# Power.net
KiCad netlist of a schematic drawn in Altium Designer
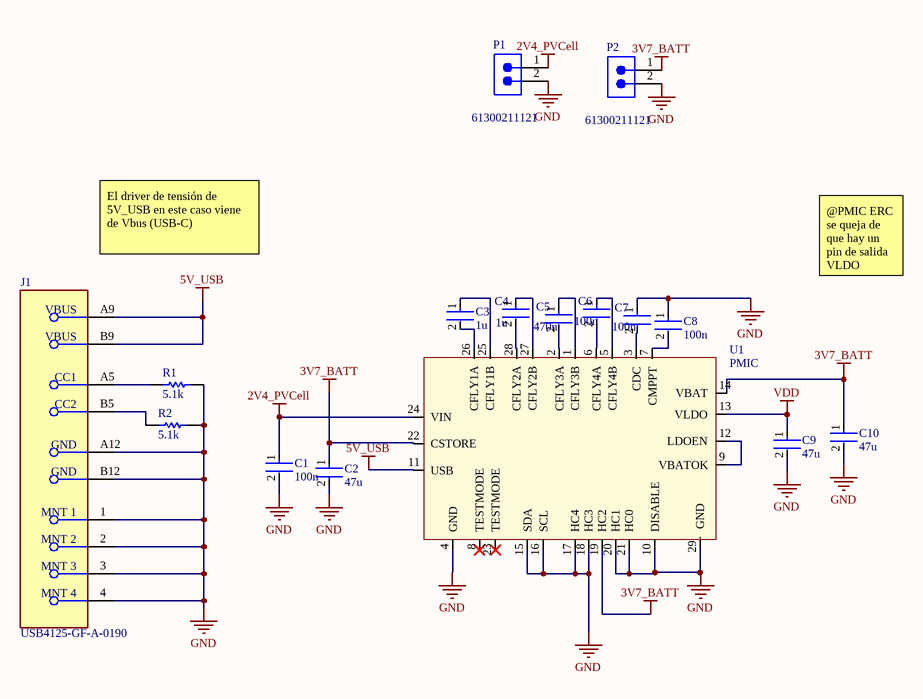
[diagram p0: Power.SchDoc]

(export (version "E")
  (design (tool "Eeschema 10.0.6"))
  (components
    (comp (ref "C1")
      (value "100n")
      (footprint "FP-GRM033-0_03-MFG")
      (description "Chip Multilayer Ceramic Capacitors for General Purpose, 0201, 0.10uF, X7S, 22%, 10%, 16V")
      (fields (field (name "TOLERANCE") "10%"))
      (libsource (lib "Altium Content Vault") (part "b4654b650e69147ec39a6b967a45e02"))
    )
    (comp (ref "C2")
      (value "47u")
      (footprint "FP-GRM188-0_2-IPC_B")
      (description "Chip Multilayer Ceramic Capacitors for General Purpose, 0603, 47uF, X5R, 15%, 20%, 6.3V")
      (fields (field (name "TOLERANCE") "20%"))
      (libsource (lib "Altium Content Vault") (part "11868f565c42a9108669ba33697ecf6"))
    )
    (comp (ref "C3")
      (value "1u")
      (footprint "FP-GRM033-0_05-e01_0_2-IPC_B")
      (description "Chip Multilayer Ceramic Capacitors for General Purpose, 0201, 1.0uF, X5R, 15%, 20%, 6.3V")
      (fields (field (name "TOLERANCE") "20%") (field (name "VOLTAGE") "6.3V"))
      (libsource (lib "Altium Content Vault") (part "02cd4be3c70576c341d710602a673aa"))
    )
    (comp (ref "C4")
      (value "1u")
      (footprint "FP-GRM033-0_05-e01_0_2-IPC_B")
      (description "Chip Multilayer Ceramic Capacitors for General Purpose, 0201, 1.0uF, X5R, 15%, 20%, 6.3V")
      (fields (field (name "TOLERANCE") "20%") (field (name "VOLTAGE") "6.3V"))
      (libsource (lib "Altium Content Vault") (part "02cd4be3c70576c341d710602a673aa"))
    )
    (comp (ref "C5")
      (value "470n")
      (footprint "FP-GRM033-0_03-IPC_C")
      (description "Chip Multilayer Ceramic Capacitors for General Purpose, 0201, 0.47uF, X5R, 15%, 10%, 6.3V")
      (fields (field (name "TOLERANCE") "10%"))
      (libsource (lib "Altium Content Vault") (part "b4654b650e69147ec39a6b967a45e02"))
    )
    (comp (ref "C6")
      (value "100n")
      (footprint "FP-GRM033-0_03-MFG")
      (description "Chip Multilayer Ceramic Capacitors for General Purpose, 0201, 0.10uF, X7S, 22%, 10%, 16V")
      (fields (field (name "TOLERANCE") "10%"))
      (libsource (lib "Altium Content Vault") (part "b4654b650e69147ec39a6b967a45e02"))
    )
    (comp (ref "C7")
      (value "100n")
      (footprint "FP-GRM033-0_03-MFG")
      (description "Chip Multilayer Ceramic Capacitors for General Purpose, 0201, 0.10uF, X7S, 22%, 10%, 16V")
      (fields (field (name "TOLERANCE") "10%"))
      (libsource (lib "Altium Content Vault") (part "b4654b650e69147ec39a6b967a45e02"))
    )
    (comp (ref "C8")
      (value "100n")
      (footprint "FP-GRM033-0_03-MFG")
      (description "Chip Multilayer Ceramic Capacitors for General Purpose, 0201, 0.10uF, X7S, 22%, 10%, 16V")
      (fields (field (name "TOLERANCE") "10%"))
      (libsource (lib "Altium Content Vault") (part "b4654b650e69147ec39a6b967a45e02"))
    )
    (comp (ref "C9")
      (value "47u")
      (footprint "FP-GRM188-0_2-IPC_B")
      (description "Chip Multilayer Ceramic Capacitors for General Purpose, 0603, 47uF, X5R, 15%, 20%, 6.3V")
      (fields (field (name "TOLERANCE") "20%"))
      (libsource (lib "Altium Content Vault") (part "11868f565c42a9108669ba33697ecf6"))
    )
    (comp (ref "C10")
      (value "47u")
      (footprint "FP-GRM188-0_2-IPC_B")
      (description "Chip Multilayer Ceramic Capacitors for General Purpose, 0603, 47uF, X5R, 15%, 20%, 6.3V")
      (fields (field (name "TOLERANCE") "20%"))
      (libsource (lib "Altium Content Vault") (part "11868f565c42a9108669ba33697ecf6"))
    )
    (comp (ref "J1")
      (value "USB4125-GF-A-0190")
      (footprint "FP-USB4125-GF-A-0190-MFG")
      (description "CONN RCPT TYPE C 6P SMD RA")
      (libsource (lib "Altium Content Vault") (part "a055484d46e58b234844902c9fd883a"))
    )
    (comp (ref "P1")
      (value "61300211121")
      (footprint "61300211121")
      (libsource (lib "Altium Content Vault") (part "Header_Male_1R_02P"))
    )
    (comp (ref "P2")
      (value "61300211121")
      (footprint "61300211121")
      (libsource (lib "Altium Content Vault") (part "Header_Male_1R_02P"))
    )
    (comp (ref "R1")
      (value "5.1k")
      (footprint "RESC1608X55X25ML10T15")
      (fields (field (name "MANUFACTURER") "Yageo") (field (name "PART NUMBER") "RC0603FR-075K1L"))
      (libsource (lib "Altium Content Vault") (part "RES"))
    )
    (comp (ref "R2")
      (value "5.1k")
      (footprint "RESC1608X55X25ML10T15")
      (fields (field (name "MANUFACTURER") "Yageo") (field (name "PART NUMBER") "RC0603FR-075K1L"))
      (libsource (lib "Altium Content Vault") (part "RES"))
    )
    (comp (ref "U1") (value "PMIC") (footprint "HVQFN-28") (libsource (lib "DEOP2425") (part "NEH7100BU")))
  )
  (nets
    (net (code "1") (name "2V4_PVCell") (class "Default")
      (node (ref "C1") (pin "1") (pinfunction "1_1") (pintype "passive"))
      (node (ref "P1") (pin "1") (pinfunction "1_1") (pintype "passive"))
      (node (ref "U1") (pin "24") (pinfunction "VIN_24") (pintype "power_in"))
    )
    (net (code "2") (name "3V7_BATT") (class "Default")
      (node (ref "C10") (pin "1") (pinfunction "1_1") (pintype "passive"))
      (node (ref "C2") (pin "1") (pinfunction "1_1") (pintype "passive"))
      (node (ref "P2") (pin "1") (pinfunction "1_1") (pintype "passive"))
      (node (ref "U1") (pin "14") (pinfunction "VBAT_14") (pintype "output"))
      (node (ref "U1") (pin "19") (pinfunction "HC2_19") (pintype "passive"))
      (node (ref "U1") (pin "22") (pinfunction "CSTORE_22") (pintype "passive"))
    )
    (net (code "3") (name "5V_USB") (class "Default")
      (node (ref "J1") (pin "A9") (pinfunction "VBUS_A9") (pintype "passive"))
      (node (ref "J1") (pin "B9") (pinfunction "VBUS_B9") (pintype "passive"))
      (node (ref "U1") (pin "11") (pinfunction "USB_11") (pintype "input"))
    )
    (net (code "4") (name "GND") (class "Default")
      (node (ref "C1") (pin "2") (pinfunction "2_2") (pintype "passive"))
      (node (ref "C10") (pin "2") (pinfunction "2_2") (pintype "passive"))
      (node (ref "C2") (pin "2") (pinfunction "2_2") (pintype "passive"))
      (node (ref "C7") (pin "1") (pinfunction "1_1") (pintype "passive"))
      (node (ref "C8") (pin "1") (pinfunction "1_1") (pintype "passive"))
      (node (ref "C9") (pin "2") (pinfunction "2_2") (pintype "passive"))
      (node (ref "J1") (pin "1") (pinfunction "MNT_1_1") (pintype "passive"))
      (node (ref "J1") (pin "2") (pinfunction "MNT_2_2") (pintype "passive"))
      (node (ref "J1") (pin "3") (pinfunction "MNT_3_3") (pintype "passive"))
      (node (ref "J1") (pin "4") (pinfunction "MNT_4_4") (pintype "passive"))
      (node (ref "J1") (pin "A12") (pinfunction "GND_A12") (pintype "passive"))
      (node (ref "J1") (pin "B12") (pinfunction "GND_B12") (pintype "passive"))
      (node (ref "P1") (pin "2") (pinfunction "2_2") (pintype "passive"))
      (node (ref "P2") (pin "2") (pinfunction "2_2") (pintype "passive"))
      (node (ref "R1") (pin "2") (pinfunction "2_2") (pintype "passive"))
      (node (ref "R2") (pin "2") (pinfunction "2_2") (pintype "passive"))
      (node (ref "U1") (pin "10") (pinfunction "DISABLE_10") (pintype "passive"))
      (node (ref "U1") (pin "15") (pinfunction "SDA_15") (pintype "bidirectional"))
      (node (ref "U1") (pin "16") (pinfunction "SCL_16") (pintype "input"))
      (node (ref "U1") (pin "17") (pinfunction "HC4_17") (pintype "passive"))
      (node (ref "U1") (pin "18") (pinfunction "HC3_18") (pintype "passive"))
      (node (ref "U1") (pin "21") (pinfunction "HC0_21") (pintype "passive"))
      (node (ref "U1") (pin "29") (pinfunction "GND_29") (pintype "passive"))
      (node (ref "U1") (pin "4") (pinfunction "GND_4") (pintype "input"))
    )
    (net (code "5") (name "Net-(J1-CC1)") (class "Default")
      (node (ref "J1") (pin "A5") (pinfunction "CC1_A5") (pintype "passive"))
      (node (ref "R1") (pin "1") (pinfunction "1_1") (pintype "passive"))
    )
    (net (code "6") (name "Net-(J1-CC2)") (class "Default")
      (node (ref "J1") (pin "B5") (pinfunction "CC2_B5") (pintype "passive"))
      (node (ref "R2") (pin "1") (pinfunction "1_1") (pintype "passive"))
    )
    (net (code "7") (name "Net-(U1-CDC)") (class "Default")
      (node (ref "C7") (pin "2") (pinfunction "2_2") (pintype "passive"))
      (node (ref "U1") (pin "3") (pinfunction "CDC_3") (pintype "passive"))
    )
    (net (code "8") (name "Net-(U1-CFLY1A)") (class "Default")
      (node (ref "C3") (pin "2") (pinfunction "2_2") (pintype "passive"))
      (node (ref "U1") (pin "26") (pinfunction "CFLY1A_26") (pintype "passive"))
    )
    (net (code "9") (name "Net-(U1-CFLY1B)") (class "Default")
      (node (ref "C3") (pin "1") (pinfunction "1_1") (pintype "passive"))
      (node (ref "U1") (pin "25") (pinfunction "CFLY1B_25") (pintype "passive"))
    )
    (net (code "10") (name "Net-(U1-CFLY2A)") (class "Default")
      (node (ref "C4") (pin "2") (pinfunction "2_2") (pintype "passive"))
      (node (ref "U1") (pin "28") (pinfunction "CFLY2A_28") (pintype "passive"))
    )
    (net (code "11") (name "Net-(U1-CFLY2B)") (class "Default")
      (node (ref "C4") (pin "1") (pinfunction "1_1") (pintype "passive"))
      (node (ref "U1") (pin "27") (pinfunction "CFLY2B_27") (pintype "passive"))
    )
    (net (code "12") (name "Net-(U1-CFLY3A)") (class "Default")
      (node (ref "C5") (pin "2") (pinfunction "2_2") (pintype "passive"))
      (node (ref "U1") (pin "2") (pinfunction "CFLY3A_2") (pintype "passive"))
    )
    (net (code "13") (name "Net-(U1-CFLY3B)") (class "Default")
      (node (ref "C5") (pin "1") (pinfunction "1_1") (pintype "passive"))
      (node (ref "U1") (pin "1") (pinfunction "CFLY3B_1") (pintype "passive"))
    )
    (net (code "14") (name "Net-(U1-CFLY4A)") (class "Default")
      (node (ref "C6") (pin "2") (pinfunction "2_2") (pintype "passive"))
      (node (ref "U1") (pin "6") (pinfunction "CFLY4A_6") (pintype "passive"))
    )
    (net (code "15") (name "Net-(U1-CFLY4B)") (class "Default")
      (node (ref "C6") (pin "1") (pinfunction "1_1") (pintype "passive"))
      (node (ref "U1") (pin "5") (pinfunction "CFLY4B_5") (pintype "passive"))
    )
    (net (code "16") (name "Net-(U1-CMPPT)") (class "Default")
      (node (ref "C8") (pin "2") (pinfunction "2_2") (pintype "passive"))
      (node (ref "U1") (pin "7") (pinfunction "CMPPT_7") (pintype "passive"))
    )
    (net (code "17") (name "Net-(U1-LDOEN)") (class "Default")
      (node (ref "U1") (pin "12") (pinfunction "LDOEN_12") (pintype "passive"))
      (node (ref "U1") (pin "9") (pinfunction "VBATOK_9") (pintype "output"))
    )
    (net (code "18") (name "VDD") (class "Default")
      (node (ref "C9") (pin "1") (pinfunction "1_1") (pintype "passive"))
      (node (ref "U1") (pin "13") (pinfunction "VLDO_13") (pintype "output"))
    )
    (net (code "19") (name "unconnected-(U1-HC1-Pad20)") (class "Default")
      (node (ref "U1") (pin "20") (pinfunction "HC1_20") (pintype "passive"))
    )
    (net (code "20") (name "unconnected-(U1-TESTMODE-Pad8)") (class "Default")
      (node (ref "U1") (pin "8") (pinfunction "TESTMODE_8") (pintype "passive+no_connect"))
    )
    (net (code "21") (name "unconnected-(U1-TESTMODE-Pad23)") (class "Default")
      (node (ref "U1") (pin "23") (pinfunction "TESTMODE_23") (pintype "passive+no_connect"))
    )
  )
)
